# 1.net
KiCad netlist of a schematic drawn in EAGLE
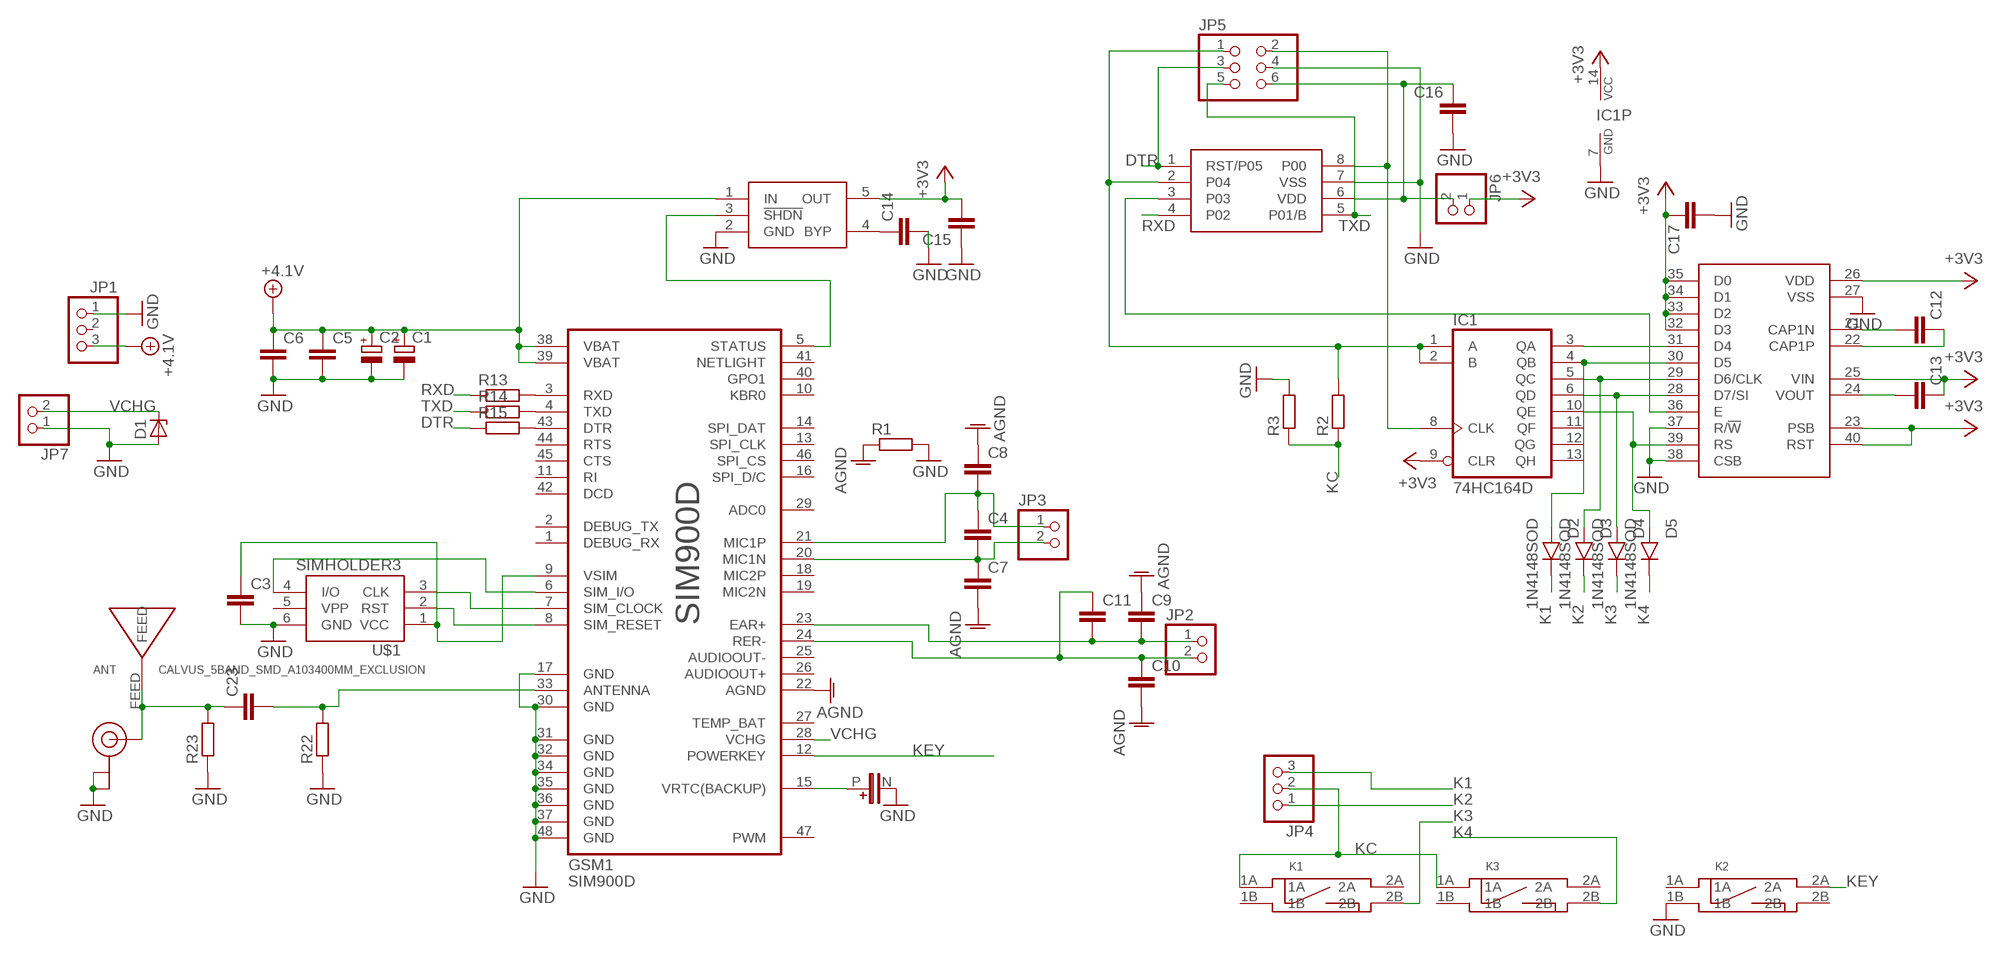
[diagram p0: schematic, sheet 1]

(export (version "E")
  (design (tool "Eeschema 10.0.6"))
  (components
    (comp (ref "ANT")
      (value "CALVUS_5BAND_SMD_A103400MM_EXCLUSION")
      (footprint "eagle-import:CALVUS_5BAND_SMD_A10340_0MM_EXCLUSION")
      (libsource (lib "eagle-import") (part "CALVUS_5BAND_SMD_A103400MM_EXCLUSION"))
    )
    (comp (ref "C1")
      (value "CPOL-EUSMCB")
      (footprint "eagle-import:SMC_B")
      (libsource (lib "eagle-import") (part "CPOL-EUSMCB"))
    )
    (comp (ref "C2")
      (value "CPOL-EUSMCB")
      (footprint "eagle-import:SMC_B")
      (libsource (lib "eagle-import") (part "CPOL-EUSMCB"))
    )
    (comp (ref "C3")
      (value "C_0806")
      (footprint "eagle-import:R0805")
      (libsource (lib "eagle-import") (part "C_0806"))
    )
    (comp (ref "C4")
      (value "C_0806")
      (footprint "eagle-import:R0805")
      (libsource (lib "eagle-import") (part "C_0806"))
    )
    (comp (ref "C5")
      (value "C_1206")
      (footprint "eagle-import:R1206")
      (libsource (lib "eagle-import") (part "C_1206"))
    )
    (comp (ref "C6")
      (value "C_1206")
      (footprint "eagle-import:R1206")
      (libsource (lib "eagle-import") (part "C_1206"))
    )
    (comp (ref "C7")
      (value "C_0806")
      (footprint "eagle-import:R0805")
      (libsource (lib "eagle-import") (part "C_0806"))
    )
    (comp (ref "C8")
      (value "C_0806")
      (footprint "eagle-import:R0805")
      (libsource (lib "eagle-import") (part "C_0806"))
    )
    (comp (ref "C9")
      (value "C_0806")
      (footprint "eagle-import:R0805")
      (libsource (lib "eagle-import") (part "C_0806"))
    )
    (comp (ref "C10")
      (value "C_0806")
      (footprint "eagle-import:R0805")
      (libsource (lib "eagle-import") (part "C_0806"))
    )
    (comp (ref "C11")
      (value "C_0806")
      (footprint "eagle-import:R0805")
      (libsource (lib "eagle-import") (part "C_0806"))
    )
    (comp (ref "C12")
      (value "C_0806")
      (footprint "eagle-import:R0805")
      (libsource (lib "eagle-import") (part "C_0806"))
    )
    (comp (ref "C13")
      (value "C_0806")
      (footprint "eagle-import:R0805")
      (libsource (lib "eagle-import") (part "C_0806"))
    )
    (comp (ref "C14")
      (value "C_0806")
      (footprint "eagle-import:R0805")
      (libsource (lib "eagle-import") (part "C_0806"))
    )
    (comp (ref "C15")
      (value "C_0806")
      (footprint "eagle-import:R0805")
      (libsource (lib "eagle-import") (part "C_0806"))
    )
    (comp (ref "C16")
      (value "C_0806")
      (footprint "eagle-import:R0805")
      (libsource (lib "eagle-import") (part "C_0806"))
    )
    (comp (ref "C17")
      (value "C_0806")
      (footprint "eagle-import:R0805")
      (libsource (lib "eagle-import") (part "C_0806"))
    )
    (comp (ref "C23")
      (value "C_0603")
      (footprint "eagle-import:0603")
      (libsource (lib "eagle-import") (part "C_0603"))
    )
    (comp (ref "D1")
      (value "ZENER-DIODESMB")
      (footprint "eagle-import:SMB")
      (libsource (lib "eagle-import") (part "ZENER-DIODESMB"))
    )
    (comp (ref "D2")
      (value "1N4148SOD")
      (footprint "eagle-import:SOD-80")
      (libsource (lib "eagle-import") (part "1N4148SOD"))
    )
    (comp (ref "D3")
      (value "1N4148SOD")
      (footprint "eagle-import:SOD-80")
      (libsource (lib "eagle-import") (part "1N4148SOD"))
    )
    (comp (ref "D4")
      (value "1N4148SOD")
      (footprint "eagle-import:SOD-80")
      (libsource (lib "eagle-import") (part "1N4148SOD"))
    )
    (comp (ref "D5")
      (value "1N4148SOD")
      (footprint "eagle-import:SOD-80")
      (libsource (lib "eagle-import") (part "1N4148SOD"))
    )
    (comp (ref "GSM1")
      (value "SIM900D")
      (footprint "eagle-import:SIM900D")
      (libsource (lib "eagle-import") (part "SIM900D"))
    )
    (comp (ref "IC1")
      (value "74HC164D")
      (footprint "eagle-import:SO14")
      (libsource (lib "eagle-import") (part "74164DHC"))
    )
    (comp (ref "JP1")
      (value "PINHD-1X03_2.54-90°")
      (footprint "eagle-import:1X03_90")
      (libsource (lib "eagle-import") (part "PINHD-1X03_2.54-90°"))
    )
    (comp (ref "JP2")
      (value "PINHD-1X02_2.00")
      (footprint "eagle-import:1X02M")
      (libsource (lib "eagle-import") (part "PINHD-1X02_2.00"))
    )
    (comp (ref "JP3")
      (value "PINHD-1X02_2.00")
      (footprint "eagle-import:1X02M")
      (libsource (lib "eagle-import") (part "PINHD-1X02_2.00"))
    )
    (comp (ref "JP4")
      (value "PINHD-1X03_2.54-90°")
      (footprint "eagle-import:1X03_90")
      (libsource (lib "eagle-import") (part "PINHD-1X03_2.54-90°"))
    )
    (comp (ref "JP5")
      (value "PINHD-2X3")
      (footprint "eagle-import:2X03")
      (libsource (lib "eagle-import") (part "PINHD-2X3"))
    )
    (comp (ref "JP6")
      (value "PINHD-1X02_2.54-S")
      (footprint "eagle-import:1X02-S")
      (libsource (lib "eagle-import") (part "PINHD-1X02_2.54-S"))
    )
    (comp (ref "JP7")
      (value "PINHD-1X02_2.54-90°")
      (footprint "eagle-import:1X02_90")
      (libsource (lib "eagle-import") (part "PINHD-1X02_2.54-90°"))
    )
    (comp (ref "K1")
      (value "SWITCH_BD_B")
      (footprint "eagle-import:SW_SMD2")
      (libsource (lib "eagle-import") (part "SWITCH_BD_B"))
    )
    (comp (ref "K2")
      (value "SWITCH_BD_B")
      (footprint "eagle-import:SW_SMD2")
      (libsource (lib "eagle-import") (part "SWITCH_BD_B"))
    )
    (comp (ref "K3")
      (value "SWITCH_BD_B")
      (footprint "eagle-import:SW_SMD2")
      (libsource (lib "eagle-import") (part "SWITCH_BD_B"))
    )
    (comp (ref "LCD2")
      (value "EAGOG_M")
      (footprint "eagle-import:EADOGM")
      (libsource (lib "eagle-import") (part "EAGOG_M"))
    )
    (comp (ref "R1")
      (value "R_0805")
      (footprint "eagle-import:R0805")
      (libsource (lib "eagle-import") (part "R_0805"))
    )
    (comp (ref "R2")
      (value "R_0805")
      (footprint "eagle-import:R0805")
      (libsource (lib "eagle-import") (part "R_0805"))
    )
    (comp (ref "R3")
      (value "R_0805")
      (footprint "eagle-import:R0805")
      (libsource (lib "eagle-import") (part "R_0805"))
    )
    (comp (ref "R13")
      (value "R_0805")
      (footprint "eagle-import:R0805")
      (libsource (lib "eagle-import") (part "R_0805"))
    )
    (comp (ref "R14")
      (value "R_0805")
      (footprint "eagle-import:R0805")
      (libsource (lib "eagle-import") (part "R_0805"))
    )
    (comp (ref "R15")
      (value "R_0805")
      (footprint "eagle-import:R0805")
      (libsource (lib "eagle-import") (part "R_0805"))
    )
    (comp (ref "R22")
      (value "R_0603")
      (footprint "eagle-import:0603")
      (libsource (lib "eagle-import") (part "R_0603"))
    )
    (comp (ref "R23")
      (value "R_0603")
      (footprint "eagle-import:0603")
      (libsource (lib "eagle-import") (part "R_0603"))
    )
    (comp (ref "U$1")
      (value "SIMHOLDER3")
      (footprint "eagle-import:SIMHOLDER3")
      (libsource (lib "eagle-import") (part "SIMHOLDER3"))
    )
    (comp (ref "U$2")
      (value "LPC810DIP")
      (footprint "eagle-import:DIL8")
      (libsource (lib "eagle-import") (part "LPC810DIP"))
    )
    (comp (ref "U$3")
      (value "TC1015")
      (footprint "eagle-import:SOT23-5")
      (libsource (lib "eagle-import") (part "TC1015"))
    )
    (comp (ref "U$4")
      (value "SUPERCAP10")
      (footprint "eagle-import:SUPERCAP_10")
      (libsource (lib "eagle-import") (part "SUPERCAP10"))
    )
    (comp (ref "U$10")
      (value "U.FL")
      (footprint "eagle-import:U.FL")
      (libsource (lib "eagle-import") (part "U.FL"))
    )
  )
  (nets
    (net (code "1") (name "+3V3") (class "Default")
      (node (ref "C13") (pin "1") (pinfunction "1_1") (pintype "passive"))
      (node (ref "C15") (pin "2") (pinfunction "2_2") (pintype "passive"))
      (node (ref "C17") (pin "1") (pinfunction "1_1") (pintype "passive"))
      (node (ref "IC1") (pin "14") (pinfunction "VCC_14") (pintype "power_in"))
      (node (ref "IC1") (pin "9") (pinfunction "CLR_9") (pintype "input"))
      (node (ref "JP6") (pin "1") (pinfunction "1_1") (pintype "passive"))
      (node (ref "LCD2") (pin "23") (pinfunction "PSB_23") (pintype "bidirectional"))
      (node (ref "LCD2") (pin "25") (pinfunction "VIN_25") (pintype "bidirectional"))
      (node (ref "LCD2") (pin "26") (pinfunction "VDD_26") (pintype "bidirectional"))
      (node (ref "LCD2") (pin "32") (pinfunction "D3_32") (pintype "bidirectional"))
      (node (ref "LCD2") (pin "33") (pinfunction "D2_33") (pintype "bidirectional"))
      (node (ref "LCD2") (pin "34") (pinfunction "D1_34") (pintype "bidirectional"))
      (node (ref "LCD2") (pin "35") (pinfunction "D0_35") (pintype "bidirectional"))
      (node (ref "LCD2") (pin "40") (pinfunction "RST_40") (pintype "bidirectional"))
      (node (ref "U$3") (pin "5") (pinfunction "OUT_5") (pintype "bidirectional"))
    )
    (net (code "2") (name "+4.1V") (class "Default")
      (node (ref "C1") (pin "+") (pinfunction "+_+") (pintype "passive"))
      (node (ref "C2") (pin "+") (pinfunction "+_+") (pintype "passive"))
      (node (ref "C5") (pin "1") (pinfunction "1_1") (pintype "passive"))
      (node (ref "C6") (pin "1") (pinfunction "1_1") (pintype "passive"))
      (node (ref "GSM1") (pin "38") (pinfunction "VBAT_38") (pintype "power_in"))
      (node (ref "GSM1") (pin "39") (pinfunction "VBAT_39") (pintype "power_in"))
      (node (ref "JP1") (pin "3") (pinfunction "3_3") (pintype "passive"))
      (node (ref "U$3") (pin "1") (pinfunction "IN_1") (pintype "bidirectional"))
    )
    (net (code "3") (name "/DTR") (class "Default")
      (node (ref "JP5") (pin "3") (pinfunction "3_3") (pintype "passive"))
      (node (ref "R15") (pin "1") (pinfunction "1_1") (pintype "passive"))
      (node (ref "U$2") (pin "1") (pinfunction "RST/P05_1") (pintype "bidirectional"))
    )
    (net (code "4") (name "/K1") (class "Default")
      (node (ref "D2") (pin "K") (pinfunction "K_K") (pintype "output"))
      (node (ref "JP4") (pin "3") (pinfunction "3_3") (pintype "passive"))
    )
    (net (code "5") (name "/K2") (class "Default")
      (node (ref "D3") (pin "K") (pinfunction "K_K") (pintype "output"))
      (node (ref "JP4") (pin "1") (pinfunction "1_1") (pintype "passive"))
    )
    (net (code "6") (name "/K3") (class "Default")
      (node (ref "D4") (pin "K") (pinfunction "K_K") (pintype "output"))
      (node (ref "K1") (pin "2B") (pinfunction "2B_2B") (pintype "bidirectional"))
    )
    (net (code "7") (name "/K4") (class "Default")
      (node (ref "D5") (pin "K") (pinfunction "K_K") (pintype "output"))
      (node (ref "K3") (pin "2B") (pinfunction "2B_2B") (pintype "bidirectional"))
    )
    (net (code "8") (name "/KC") (class "Default")
      (node (ref "JP4") (pin "2") (pinfunction "2_2") (pintype "passive"))
      (node (ref "K1") (pin "1A") (pinfunction "1A_1A") (pintype "bidirectional"))
      (node (ref "K3") (pin "1A") (pinfunction "1A_1A") (pintype "bidirectional"))
      (node (ref "R2") (pin "1") (pinfunction "1_1") (pintype "passive"))
      (node (ref "R3") (pin "1") (pinfunction "1_1") (pintype "passive"))
    )
    (net (code "9") (name "/KEY") (class "Default")
      (node (ref "GSM1") (pin "12") (pinfunction "POWERKEY_12") (pintype "input"))
      (node (ref "K2") (pin "2A") (pinfunction "2A_2A") (pintype "bidirectional"))
    )
    (net (code "10") (name "/NETLIGHT") (class "Default")
      (node (ref "GSM1") (pin "41") (pinfunction "NETLIGHT_41") (pintype "power_in"))
    )
    (net (code "11") (name "/RXD") (class "Default")
      (node (ref "R13") (pin "1") (pinfunction "1_1") (pintype "passive"))
      (node (ref "U$2") (pin "4") (pinfunction "P02_4") (pintype "bidirectional"))
    )
    (net (code "12") (name "/TXD") (class "Default")
      (node (ref "JP5") (pin "5") (pinfunction "5_5") (pintype "passive"))
      (node (ref "R14") (pin "1") (pinfunction "1_1") (pintype "passive"))
      (node (ref "U$2") (pin "5") (pinfunction "P01/B_5") (pintype "bidirectional"))
    )
    (net (code "13") (name "/VCHG") (class "Default")
      (node (ref "D1") (pin "C") (pinfunction "C_C") (pintype "passive"))
      (node (ref "GSM1") (pin "28") (pinfunction "VCHG_28") (pintype "output"))
      (node (ref "JP7") (pin "2") (pinfunction "2_2") (pintype "passive"))
    )
    (net (code "14") (name "AGND") (class "Default")
      (node (ref "C10") (pin "2") (pinfunction "2_2") (pintype "passive"))
      (node (ref "C7") (pin "2") (pinfunction "2_2") (pintype "passive"))
      (node (ref "C8") (pin "1") (pinfunction "1_1") (pintype "passive"))
      (node (ref "C9") (pin "1") (pinfunction "1_1") (pintype "passive"))
      (node (ref "GSM1") (pin "22") (pinfunction "AGND_22") (pintype "power_in"))
      (node (ref "R1") (pin "1") (pinfunction "1_1") (pintype "passive"))
    )
    (net (code "15") (name "GND") (class "Default")
      (node (ref "C1") (pin "-") (pinfunction "-_-") (pintype "passive"))
      (node (ref "C14") (pin "2") (pinfunction "2_2") (pintype "passive"))
      (node (ref "C15") (pin "1") (pinfunction "1_1") (pintype "passive"))
      (node (ref "C16") (pin "2") (pinfunction "2_2") (pintype "passive"))
      (node (ref "C17") (pin "2") (pinfunction "2_2") (pintype "passive"))
      (node (ref "C2") (pin "-") (pinfunction "-_-") (pintype "passive"))
      (node (ref "C3") (pin "2") (pinfunction "2_2") (pintype "passive"))
      (node (ref "C5") (pin "2") (pinfunction "2_2") (pintype "passive"))
      (node (ref "C6") (pin "2") (pinfunction "2_2") (pintype "passive"))
      (node (ref "D1") (pin "A") (pinfunction "A_A") (pintype "passive"))
      (node (ref "GSM1") (pin "17") (pinfunction "GND_17") (pintype "power_in"))
      (node (ref "GSM1") (pin "30") (pinfunction "GND_30") (pintype "power_in"))
      (node (ref "GSM1") (pin "31") (pinfunction "GND_31") (pintype "power_in"))
      (node (ref "GSM1") (pin "32") (pinfunction "GND_32") (pintype "power_in"))
      (node (ref "GSM1") (pin "34") (pinfunction "GND_34") (pintype "power_in"))
      (node (ref "GSM1") (pin "35") (pinfunction "GND_35") (pintype "power_in"))
      (node (ref "GSM1") (pin "36") (pinfunction "GND_36") (pintype "power_in"))
      (node (ref "GSM1") (pin "37") (pinfunction "GND_37") (pintype "power_in"))
      (node (ref "GSM1") (pin "48") (pinfunction "GND_48") (pintype "power_in"))
      (node (ref "IC1") (pin "7") (pinfunction "GND_7") (pintype "power_in"))
      (node (ref "JP1") (pin "1") (pinfunction "1_1") (pintype "passive"))
      (node (ref "JP5") (pin "4") (pinfunction "4_4") (pintype "passive"))
      (node (ref "JP7") (pin "1") (pinfunction "1_1") (pintype "passive"))
      (node (ref "K2") (pin "1B") (pinfunction "1B_1B") (pintype "bidirectional"))
      (node (ref "LCD2") (pin "27") (pinfunction "VSS_27") (pintype "bidirectional"))
      (node (ref "LCD2") (pin "37") (pinfunction "R/~{W}_37") (pintype "bidirectional"))
      (node (ref "LCD2") (pin "38") (pinfunction "CSB_38") (pintype "bidirectional"))
      (node (ref "R1") (pin "2") (pinfunction "2_2") (pintype "passive"))
      (node (ref "R22") (pin "1") (pinfunction "1_1") (pintype "passive"))
      (node (ref "R23") (pin "1") (pinfunction "1_1") (pintype "passive"))
      (node (ref "R3") (pin "2") (pinfunction "2_2") (pintype "passive"))
      (node (ref "U$1") (pin "6") (pinfunction "GND_6") (pintype "bidirectional"))
      (node (ref "U$10") (pin "P$1") (pinfunction "GND_P$1") (pintype "bidirectional"))
      (node (ref "U$10") (pin "P$2") (pinfunction "GND_P$2") (pintype "bidirectional"))
      (node (ref "U$2") (pin "7") (pinfunction "VSS_7") (pintype "bidirectional"))
      (node (ref "U$3") (pin "2") (pinfunction "GND_2") (pintype "bidirectional"))
      (node (ref "U$4") (pin "N") (pinfunction "N_N") (pintype "bidirectional"))
    )
    (net (code "16") (name "Net-(GSM1-ANTENNA)") (class "Default")
      (node (ref "C23") (pin "2") (pinfunction "2_2") (pintype "passive"))
      (node (ref "GSM1") (pin "33") (pinfunction "ANTENNA_33") (pintype "power_in"))
      (node (ref "R22") (pin "2") (pinfunction "2_2") (pintype "passive"))
    )
    (net (code "17") (name "Net-(GSM1-DTR)") (class "Default")
      (node (ref "GSM1") (pin "43") (pinfunction "DTR_43") (pintype "input"))
      (node (ref "R15") (pin "2") (pinfunction "2_2") (pintype "passive"))
    )
    (net (code "18") (name "Net-(GSM1-EAR+)") (class "Default")
      (node (ref "C11") (pin "2") (pinfunction "2_2") (pintype "passive"))
      (node (ref "C9") (pin "2") (pinfunction "2_2") (pintype "passive"))
      (node (ref "GSM1") (pin "23") (pinfunction "EAR+_23") (pintype "output"))
      (node (ref "JP2") (pin "1") (pinfunction "1_1") (pintype "passive"))
    )
    (net (code "19") (name "Net-(GSM1-MIC1N)") (class "Default")
      (node (ref "C4") (pin "2") (pinfunction "2_2") (pintype "passive"))
      (node (ref "C7") (pin "1") (pinfunction "1_1") (pintype "passive"))
      (node (ref "GSM1") (pin "20") (pinfunction "MIC1N_20") (pintype "input"))
      (node (ref "JP3") (pin "2") (pinfunction "2_2") (pintype "passive"))
    )
    (net (code "20") (name "Net-(GSM1-MIC1P)") (class "Default")
      (node (ref "C4") (pin "1") (pinfunction "1_1") (pintype "passive"))
      (node (ref "C8") (pin "2") (pinfunction "2_2") (pintype "passive"))
      (node (ref "GSM1") (pin "21") (pinfunction "MIC1P_21") (pintype "input"))
      (node (ref "JP3") (pin "1") (pinfunction "1_1") (pintype "passive"))
    )
    (net (code "21") (name "Net-(GSM1-RER-)") (class "Default")
      (node (ref "C10") (pin "1") (pinfunction "1_1") (pintype "passive"))
      (node (ref "C11") (pin "1") (pinfunction "1_1") (pintype "passive"))
      (node (ref "GSM1") (pin "24") (pinfunction "RER-_24") (pintype "output"))
      (node (ref "JP2") (pin "2") (pinfunction "2_2") (pintype "passive"))
    )
    (net (code "22") (name "Net-(GSM1-RXD)") (class "Default")
      (node (ref "GSM1") (pin "3") (pinfunction "RXD_3") (pintype "input"))
      (node (ref "R13") (pin "2") (pinfunction "2_2") (pintype "passive"))
    )
    (net (code "23") (name "Net-(GSM1-SIM_CLOCK)") (class "Default")
      (node (ref "GSM1") (pin "7") (pinfunction "SIM_CLOCK_7") (pintype "output"))
      (node (ref "U$1") (pin "3") (pinfunction "CLK_3") (pintype "bidirectional"))
    )
    (net (code "24") (name "Net-(GSM1-SIM_I{slash}O)") (class "Default")
      (node (ref "GSM1") (pin "6") (pinfunction "SIM_I/O_6") (pintype "bidirectional"))
      (node (ref "U$1") (pin "4") (pinfunction "I/O_4") (pintype "bidirectional"))
    )
    (net (code "25") (name "Net-(GSM1-SIM_RESET)") (class "Default")
      (node (ref "GSM1") (pin "8") (pinfunction "SIM_RESET_8") (pintype "output"))
      (node (ref "U$1") (pin "2") (pinfunction "RST_2") (pintype "bidirectional"))
    )
    (net (code "26") (name "Net-(GSM1-STATUS)") (class "Default")
      (node (ref "GSM1") (pin "5") (pinfunction "STATUS_5") (pintype "output"))
      (node (ref "U$3") (pin "3") (pinfunction "~{SHDN}_3") (pintype "bidirectional"))
    )
    (net (code "27") (name "Net-(GSM1-TXD)") (class "Default")
      (node (ref "GSM1") (pin "4") (pinfunction "TXD_4") (pintype "output"))
      (node (ref "R14") (pin "2") (pinfunction "2_2") (pintype "passive"))
    )
    (net (code "28") (name "Net-(GSM1-VRTC(BACKUP))") (class "Default")
      (node (ref "GSM1") (pin "15") (pinfunction "VRTC(BACKUP)_15") (pintype "power_in"))
      (node (ref "U$4") (pin "P") (pinfunction "P_P") (pintype "bidirectional"))
    )
    (net (code "29") (name "Net-(GSM1-VSIM)") (class "Default")
      (node (ref "C3") (pin "1") (pinfunction "1_1") (pintype "passive"))
      (node (ref "GSM1") (pin "9") (pinfunction "VSIM_9") (pintype "output"))
      (node (ref "U$1") (pin "1") (pinfunction "VCC_1") (pintype "bidirectional"))
    )
    (net (code "30") (name "Net-(IC1A-A)") (class "Default")
      (node (ref "IC1") (pin "1") (pinfunction "A_1") (pintype "input"))
      (node (ref "IC1") (pin "2") (pinfunction "B_2") (pintype "input"))
      (node (ref "JP5") (pin "1") (pinfunction "1_1") (pintype "passive"))
      (node (ref "R2") (pin "2") (pinfunction "2_2") (pintype "passive"))
      (node (ref "U$2") (pin "2") (pinfunction "P04_2") (pintype "bidirectional"))
    )
    (net (code "31") (name "Net-(IC1A-CLK)") (class "Default")
      (node (ref "IC1") (pin "8") (pinfunction "CLK_8") (pintype "input"))
      (node (ref "JP5") (pin "2") (pinfunction "2_2") (pintype "passive"))
      (node (ref "U$2") (pin "8") (pinfunction "P00_8") (pintype "bidirectional"))
    )
    (net (code "32") (name "Net-(IC1A-QA)") (class "Default")
      (node (ref "IC1") (pin "3") (pinfunction "QA_3") (pintype "output"))
      (node (ref "LCD2") (pin "31") (pinfunction "D4_31") (pintype "bidirectional"))
    )
    (net (code "33") (name "Net-(IC1A-QB)") (class "Default")
      (node (ref "D2") (pin "A") (pinfunction "A_A") (pintype "input"))
      (node (ref "IC1") (pin "4") (pinfunction "QB_4") (pintype "output"))
      (node (ref "LCD2") (pin "30") (pinfunction "D5_30") (pintype "bidirectional"))
    )
    (net (code "34") (name "Net-(IC1A-QC)") (class "Default")
      (node (ref "D3") (pin "A") (pinfunction "A_A") (pintype "input"))
      (node (ref "IC1") (pin "5") (pinfunction "QC_5") (pintype "output"))
      (node (ref "LCD2") (pin "29") (pinfunction "D6/CLK_29") (pintype "bidirectional"))
    )
    (net (code "35") (name "Net-(IC1A-QD)") (class "Default")
      (node (ref "D4") (pin "A") (pinfunction "A_A") (pintype "input"))
      (node (ref "IC1") (pin "6") (pinfunction "QD_6") (pintype "output"))
      (node (ref "LCD2") (pin "28") (pinfunction "D7/SI_28") (pintype "bidirectional"))
    )
    (net (code "36") (name "Net-(IC1A-QE)") (class "Default")
      (node (ref "D5") (pin "A") (pinfunction "A_A") (pintype "input"))
      (node (ref "IC1") (pin "10") (pinfunction "QE_10") (pintype "output"))
      (node (ref "LCD2") (pin "39") (pinfunction "RS_39") (pintype "bidirectional"))
    )
    (net (code "37") (name "Net-(LCD2-CAP1N)") (class "Default")
      (node (ref "C12") (pin "2") (pinfunction "2_2") (pintype "passive"))
      (node (ref "LCD2") (pin "21") (pinfunction "CAP1N_21") (pintype "bidirectional"))
    )
    (net (code "38") (name "Net-(LCD2-CAP1P)") (class "Default")
      (node (ref "C12") (pin "1") (pinfunction "1_1") (pintype "passive"))
      (node (ref "LCD2") (pin "22") (pinfunction "CAP1P_22") (pintype "bidirectional"))
    )
    (net (code "39") (name "Net-(LCD2-E)") (class "Default")
      (node (ref "LCD2") (pin "36") (pinfunction "E_36") (pintype "bidirectional"))
      (node (ref "U$2") (pin "3") (pinfunction "P03_3") (pintype "bidirectional"))
    )
    (net (code "40") (name "Net-(LCD2-VOUT)") (class "Default")
      (node (ref "C13") (pin "2") (pinfunction "2_2") (pintype "passive"))
      (node (ref "LCD2") (pin "24") (pinfunction "VOUT_24") (pintype "bidirectional"))
    )
    (net (code "41") (name "Net-(U$2-VDD)") (class "Default")
      (node (ref "C16") (pin "1") (pinfunction "1_1") (pintype "passive"))
      (node (ref "JP5") (pin "6") (pinfunction "6_6") (pintype "passive"))
      (node (ref "JP6") (pin "2") (pinfunction "2_2") (pintype "passive"))
      (node (ref "U$2") (pin "6") (pinfunction "VDD_6") (pintype "bidirectional"))
    )
    (net (code "42") (name "Net-(U$3-BYP)") (class "Default")
      (node (ref "C14") (pin "1") (pinfunction "1_1") (pintype "passive"))
      (node (ref "U$3") (pin "4") (pinfunction "BYP_4") (pintype "bidirectional"))
    )
    (net (code "43") (name "Net-(U$10-SIGNAL)") (class "Default")
      (node (ref "ANT") (pin "FEED") (pinfunction "FEED_FEED") (pintype "bidirectional"))
      (node (ref "C23") (pin "1") (pinfunction "1_1") (pintype "passive"))
      (node (ref "R23") (pin "2") (pinfunction "2_2") (pintype "passive"))
      (node (ref "U$10") (pin "P$3") (pinfunction "SIGNAL_P$3") (pintype "bidirectional"))
    )
    (net (code "44") (name "unconnected-(GSM1-ADC0-Pad29)") (class "Default")
      (node (ref "GSM1") (pin "29") (pinfunction "ADC0_29") (pintype "input"))
    )
    (net (code "45") (name "unconnected-(GSM1-AUDIOOUT+-Pad26)") (class "Default")
      (node (ref "GSM1") (pin "26") (pinfunction "AUDIOOUT+_26") (pintype "output"))
    )
    (net (code "46") (name "unconnected-(GSM1-AUDIOOUT--Pad25)") (class "Default")
      (node (ref "GSM1") (pin "25") (pinfunction "AUDIOOUT-_25") (pintype "output"))
    )
    (net (code "47") (name "unconnected-(GSM1-CTS-Pad45)") (class "Default")
      (node (ref "GSM1") (pin "45") (pinfunction "CTS_45") (pintype "output"))
    )
    (net (code "48") (name "unconnected-(GSM1-DCD-Pad42)") (class "Default")
      (node (ref "GSM1") (pin "42") (pinfunction "DCD_42") (pintype "input"))
    )
    (net (code "49") (name "unconnected-(GSM1-DEBUG_RX-Pad1)") (class "Default")
      (node (ref "GSM1") (pin "1") (pinfunction "DEBUG_RX_1") (pintype "input"))
    )
    (net (code "50") (name "unconnected-(GSM1-DEBUG_TX-Pad2)") (class "Default")
      (node (ref "GSM1") (pin "2") (pinfunction "DEBUG_TX_2") (pintype "output"))
    )
    (net (code "51") (name "unconnected-(GSM1-GPO1-Pad40)") (class "Default")
      (node (ref "GSM1") (pin "40") (pinfunction "GPO1_40") (pintype "output"))
    )
    (net (code "52") (name "unconnected-(GSM1-KBR0-Pad10)") (class "Default")
      (node (ref "GSM1") (pin "10") (pinfunction "KBR0_10") (pintype "input"))
    )
    (net (code "53") (name "unconnected-(GSM1-MIC2N-Pad19)") (class "Default")
      (node (ref "GSM1") (pin "19") (pinfunction "MIC2N_19") (pintype "input"))
    )
    (net (code "54") (name "unconnected-(GSM1-MIC2P-Pad18)") (class "Default")
      (node (ref "GSM1") (pin "18") (pinfunction "MIC2P_18") (pintype "input"))
    )
    (net (code "55") (name "unconnected-(GSM1-PWM-Pad47)") (class "Default")
      (node (ref "GSM1") (pin "47") (pinfunction "PWM_47") (pintype "input"))
    )
    (net (code "56") (name "unconnected-(GSM1-RI-Pad11)") (class "Default")
      (node (ref "GSM1") (pin "11") (pinfunction "RI_11") (pintype "output"))
    )
    (net (code "57") (name "unconnected-(GSM1-RTS-Pad44)") (class "Default")
      (node (ref "GSM1") (pin "44") (pinfunction "RTS_44") (pintype "input"))
    )
    (net (code "58") (name "unconnected-(GSM1-SPI_CLK-Pad13)") (class "Default")
      (node (ref "GSM1") (pin "13") (pinfunction "SPI_CLK_13") (pintype "output"))
    )
    (net (code "59") (name "unconnected-(GSM1-SPI_CS-Pad46)") (class "Default")
      (node (ref "GSM1") (pin "46") (pinfunction "SPI_CS_46") (pintype "output"))
    )
    (net (code "60") (name "unconnected-(GSM1-SPI_DAT-Pad14)") (class "Default")
      (node (ref "GSM1") (pin "14") (pinfunction "SPI_DAT_14") (pintype "bidirectional"))
    )
    (net (code "61") (name "unconnected-(GSM1-SPI_D{slash}C-Pad16)") (class "Default")
      (node (ref "GSM1") (pin "16") (pinfunction "SPI_D/C_16") (pintype "input"))
    )
    (net (code "62") (name "unconnected-(GSM1-TEMP_BAT-Pad27)") (class "Default")
      (node (ref "GSM1") (pin "27") (pinfunction "TEMP_BAT_27") (pintype "output"))
    )
    (net (code "63") (name "unconnected-(IC1A-QF-Pad11)") (class "Default")
      (node (ref "IC1") (pin "11") (pinfunction "QF_11") (pintype "output"))
    )
    (net (code "64") (name "unconnected-(IC1A-QG-Pad12)") (class "Default")
      (node (ref "IC1") (pin "12") (pinfunction "QG_12") (pintype "output"))
    )
    (net (code "65") (name "unconnected-(IC1A-QH-Pad13)") (class "Default")
      (node (ref "IC1") (pin "13") (pinfunction "QH_13") (pintype "output"))
    )
    (net (code "66") (name "unconnected-(JP1-Pad2)") (class "Default")
      (node (ref "JP1") (pin "2") (pinfunction "2_2") (pintype "passive"))
    )
    (net (code "67") (name "unconnected-(K1-Pad1B)") (class "Default")
      (node (ref "K1") (pin "1B") (pinfunction "1B_1B") (pintype "bidirectional"))
    )
    (net (code "68") (name "unconnected-(K1-Pad2A)") (class "Default")
      (node (ref "K1") (pin "2A") (pinfunction "2A_2A") (pintype "bidirectional"))
    )
    (net (code "69") (name "unconnected-(K2-Pad1A)") (class "Default")
      (node (ref "K2") (pin "1A") (pinfunction "1A_1A") (pintype "bidirectional"))
    )
    (net (code "70") (name "unconnected-(K2-Pad2B)") (class "Default")
      (node (ref "K2") (pin "2B") (pinfunction "2B_2B") (pintype "bidirectional"))
    )
    (net (code "71") (name "unconnected-(K3-Pad1B)") (class "Default")
      (node (ref "K3") (pin "1B") (pinfunction "1B_1B") (pintype "bidirectional"))
    )
    (net (code "72") (name "unconnected-(K3-Pad2A)") (class "Default")
      (node (ref "K3") (pin "2A") (pinfunction "2A_2A") (pintype "bidirectional"))
    )
    (net (code "73") (name "unconnected-(U$1-VPP-Pad5)") (class "Default")
      (node (ref "U$1") (pin "5") (pinfunction "VPP_5") (pintype "bidirectional"))
    )
  )
)
